# cbm_usb_v1_1a.net
KiCad netlist of a schematic drawn in EAGLE
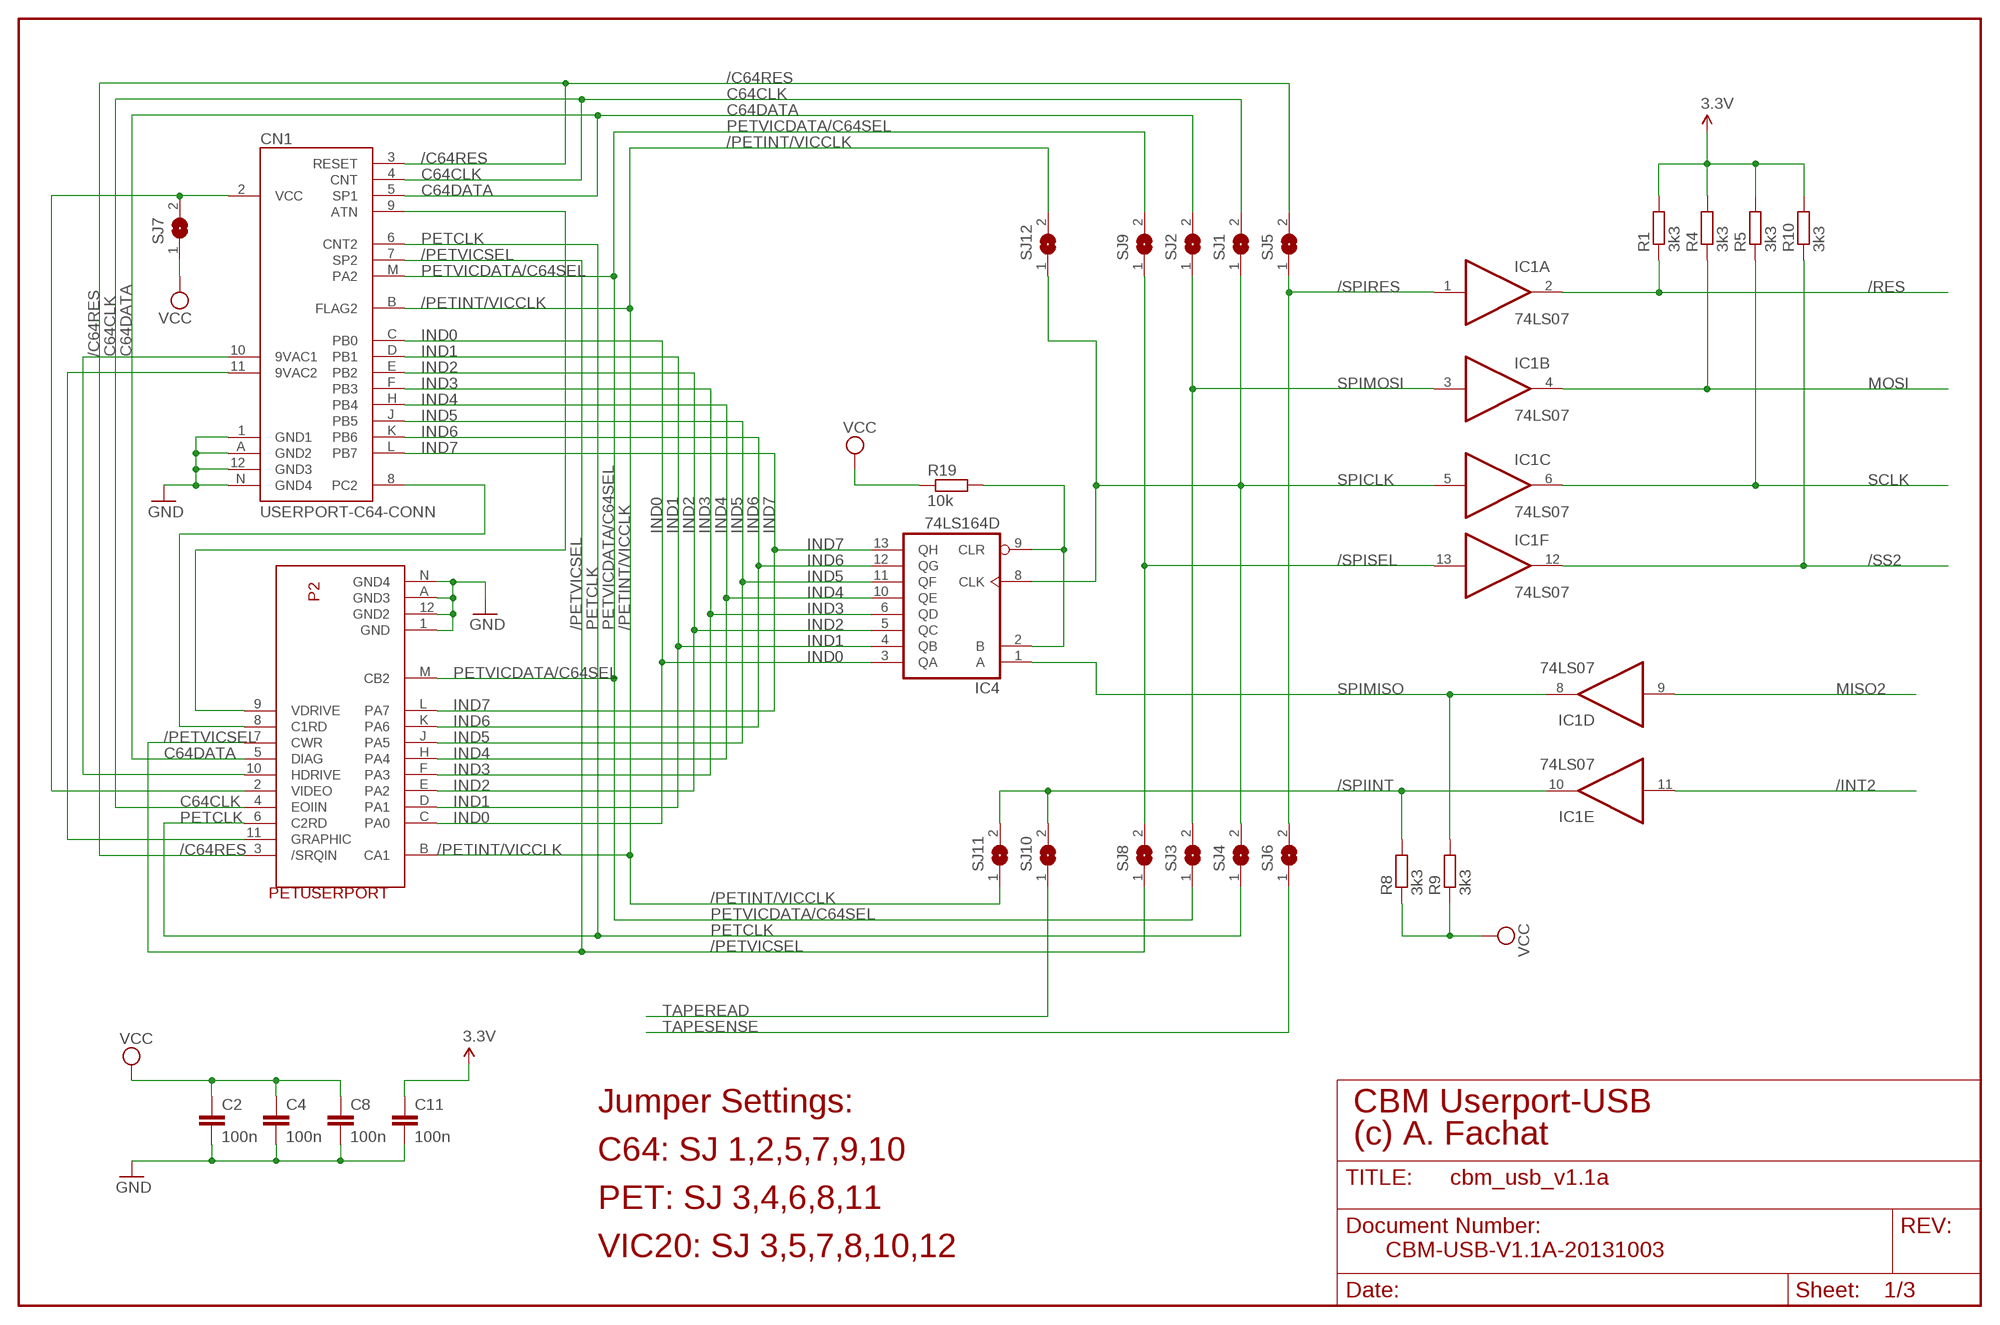
[diagram p0: schematic, sheet 1]
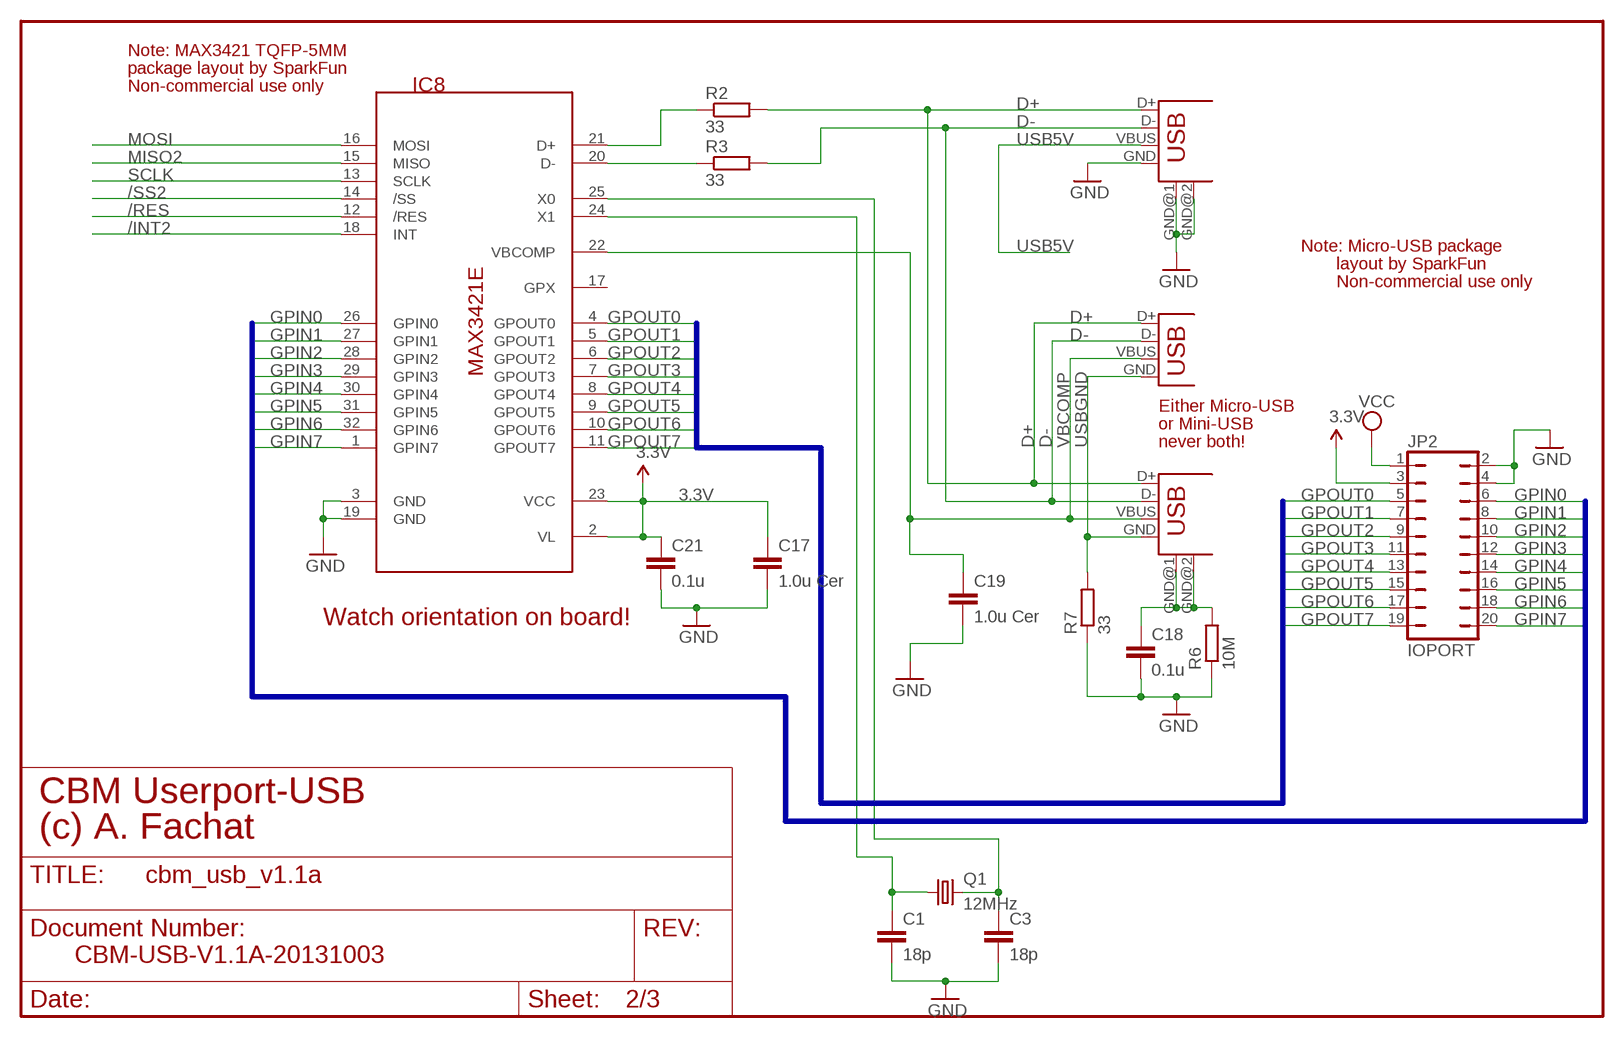
[diagram p1: schematic, sheet 2]
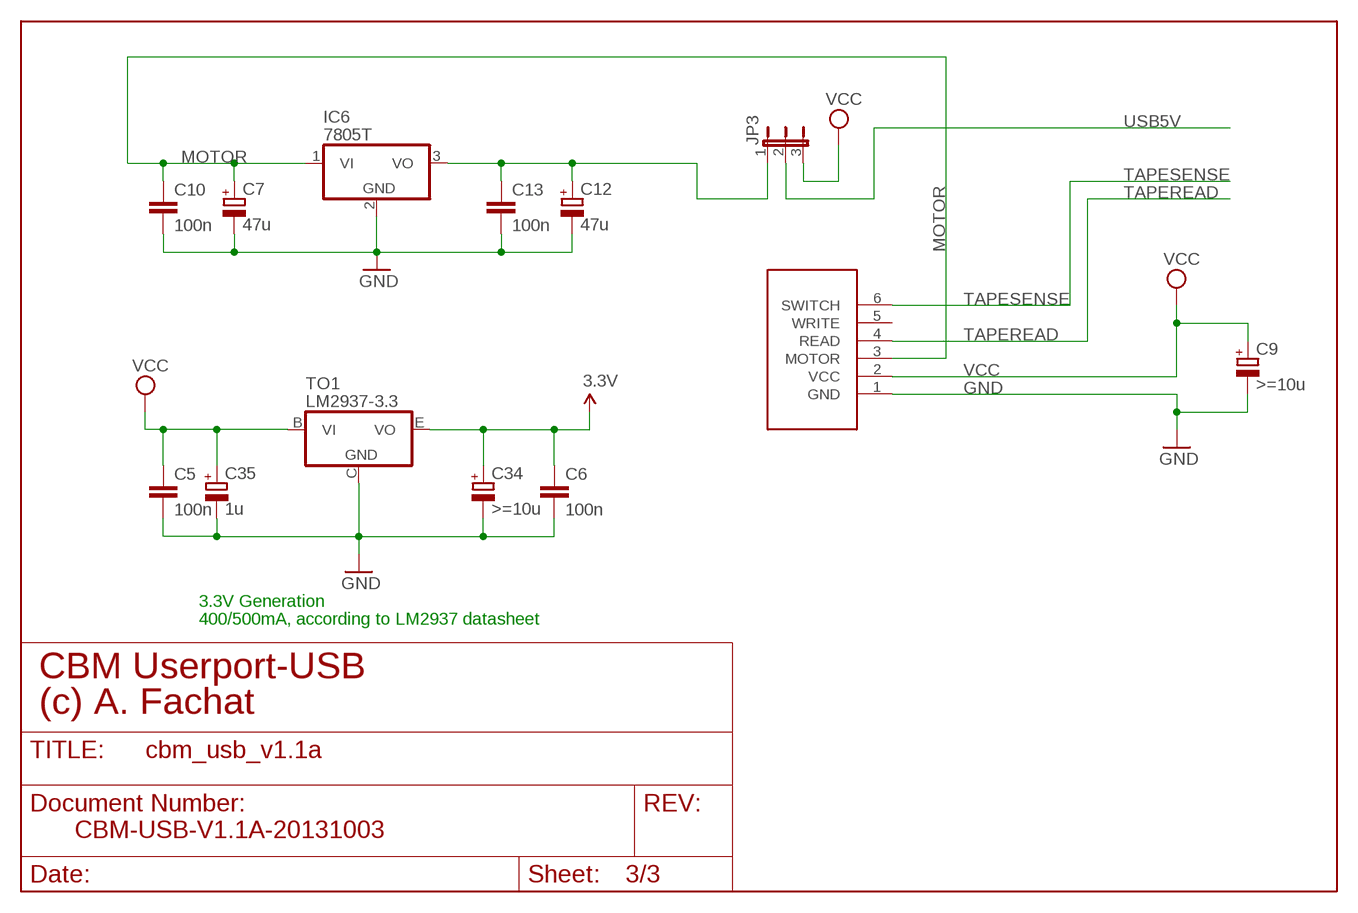
[diagram p2: schematic, sheet 3]

(export (version "E")
  (design (tool "Eeschema 10.0.6"))
  (components
    (comp (ref "C2")
      (value "100n")
      (footprint "eagle-import:C050-025X075")
      (libsource (lib "eagle-import") (part "C-EU050-025X075"))
    )
    (comp (ref "C4")
      (value "100n")
      (footprint "eagle-import:C050-025X075")
      (libsource (lib "eagle-import") (part "C-EU050-025X075"))
    )
    (comp (ref "C8")
      (value "100n")
      (footprint "eagle-import:C050-025X075")
      (libsource (lib "eagle-import") (part "C-EU050-025X075"))
    )
    (comp (ref "C11")
      (value "100n")
      (footprint "eagle-import:C050-025X075")
      (libsource (lib "eagle-import") (part "C-EU050-025X075"))
    )
    (comp (ref "CN1")
      (value "USERPORT-C64-CONN")
      (footprint "eagle-import:UPS24CONN")
      (libsource (lib "eagle-import") (part "USERPORT-C64-CONN"))
    )
    (comp (ref "IC1")
      (value "74LS07")
      (footprint "eagle-import:SO14")
      (libsource (lib "eagle-import") (part "7407DLS"))
    )
    (comp (ref "IC4")
      (value "74LS164D")
      (footprint "eagle-import:SO14")
      (libsource (lib "eagle-import") (part "74164DLS"))
    )
    (comp (ref "P2")
      (value "PETUSERPORT")
      (footprint "eagle-import:FLAT24")
      (libsource (lib "eagle-import") (part "PETUSERPORT"))
    )
    (comp (ref "R1")
      (value "3k3")
      (footprint "eagle-import:0204_7")
      (libsource (lib "eagle-import") (part "R-EU_0204/7"))
    )
    (comp (ref "R4")
      (value "3k3")
      (footprint "eagle-import:0204_7")
      (libsource (lib "eagle-import") (part "R-EU_0204/7"))
    )
    (comp (ref "R5")
      (value "3k3")
      (footprint "eagle-import:0204_7")
      (libsource (lib "eagle-import") (part "R-EU_0204/7"))
    )
    (comp (ref "R8")
      (value "3k3")
      (footprint "eagle-import:0204_7")
      (libsource (lib "eagle-import") (part "R-EU_0204/7"))
    )
    (comp (ref "R9")
      (value "3k3")
      (footprint "eagle-import:0204_7")
      (libsource (lib "eagle-import") (part "R-EU_0204/7"))
    )
    (comp (ref "R10")
      (value "3k3")
      (footprint "eagle-import:0204_7")
      (libsource (lib "eagle-import") (part "R-EU_0204/7"))
    )
    (comp (ref "R19")
      (value "10k")
      (footprint "eagle-import:0204_7")
      (libsource (lib "eagle-import") (part "R-EU_0204/7"))
    )
    (comp (ref "SJ1")
      (value "SJW")
      (footprint "eagle-import:SJW")
      (libsource (lib "eagle-import") (part "SJW"))
    )
    (comp (ref "SJ2")
      (value "SJW")
      (footprint "eagle-import:SJW")
      (libsource (lib "eagle-import") (part "SJW"))
    )
    (comp (ref "SJ3")
      (value "SJW")
      (footprint "eagle-import:SJW")
      (libsource (lib "eagle-import") (part "SJW"))
    )
    (comp (ref "SJ4")
      (value "SJW")
      (footprint "eagle-import:SJW")
      (libsource (lib "eagle-import") (part "SJW"))
    )
    (comp (ref "SJ5")
      (value "SJW")
      (footprint "eagle-import:SJW")
      (libsource (lib "eagle-import") (part "SJW"))
    )
    (comp (ref "SJ6")
      (value "SJW")
      (footprint "eagle-import:SJW")
      (libsource (lib "eagle-import") (part "SJW"))
    )
    (comp (ref "SJ7")
      (value "SJW")
      (footprint "eagle-import:SJW")
      (libsource (lib "eagle-import") (part "SJW"))
    )
    (comp (ref "SJ8")
      (value "SJW")
      (footprint "eagle-import:SJW")
      (libsource (lib "eagle-import") (part "SJW"))
    )
    (comp (ref "SJ9")
      (value "SJW")
      (footprint "eagle-import:SJW")
      (libsource (lib "eagle-import") (part "SJW"))
    )
    (comp (ref "SJ10")
      (value "SJW")
      (footprint "eagle-import:SJW")
      (libsource (lib "eagle-import") (part "SJW"))
    )
    (comp (ref "SJ11")
      (value "SJW")
      (footprint "eagle-import:SJW")
      (libsource (lib "eagle-import") (part "SJW"))
    )
    (comp (ref "SJ12")
      (value "SJW")
      (footprint "eagle-import:SJW")
      (libsource (lib "eagle-import") (part "SJW"))
    )
    (comp (ref "C1")
      (value "18p")
      (footprint "eagle-import:C050-025X075")
      (libsource (lib "eagle-import") (part "C-EU050-025X075"))
    )
    (comp (ref "C3")
      (value "18p")
      (footprint "eagle-import:C050-025X075")
      (libsource (lib "eagle-import") (part "C-EU050-025X075"))
    )
    (comp (ref "C17")
      (value "1.0u Cer")
      (footprint "eagle-import:C050-024X044")
      (libsource (lib "eagle-import") (part "C-EU050-024X044"))
    )
    (comp (ref "C18")
      (value "0.1u")
      (footprint "eagle-import:C050-025X075")
      (libsource (lib "eagle-import") (part "C-EU050-025X075"))
    )
    (comp (ref "C19")
      (value "1.0u Cer")
      (footprint "eagle-import:C050-024X044")
      (libsource (lib "eagle-import") (part "C-EU050-024X044"))
    )
    (comp (ref "C21")
      (value "0.1u")
      (footprint "eagle-import:C050-025X075")
      (libsource (lib "eagle-import") (part "C-EU050-025X075"))
    )
    (comp (ref "IC8")
      (value "MAX3421E")
      (footprint "eagle-import:TQFP32-5MM")
      (libsource (lib "eagle-import") (part "MAX3421E"))
    )
    (comp (ref "JP2")
      (value "IOPORT")
      (footprint "eagle-import:JP10Q")
      (libsource (lib "eagle-import") (part "JP10Q"))
    )
    (comp (ref "Q1")
      (value "12MHz")
      (footprint "eagle-import:HC49U70")
      (libsource (lib "eagle-import") (part "CRYSTALHC49U70"))
    )
    (comp (ref "R2")
      (value "33")
      (footprint "eagle-import:0204_7")
      (libsource (lib "eagle-import") (part "R-EU_0204/7"))
    )
    (comp (ref "R3")
      (value "33")
      (footprint "eagle-import:0204_7")
      (libsource (lib "eagle-import") (part "R-EU_0204/7"))
    )
    (comp (ref "R6")
      (value "10M")
      (footprint "eagle-import:0204_7")
      (libsource (lib "eagle-import") (part "R-EU_0204/7"))
    )
    (comp (ref "R7")
      (value "33")
      (footprint "eagle-import:0204_7")
      (libsource (lib "eagle-import") (part "R-EU_0204/7"))
    )
    (comp (ref "USB1")
      (value "USB-A-H")
      (footprint "eagle-import:USB-A-H")
      (libsource (lib "eagle-import") (part "con-usb-2_USB-A-H"))
    )
    (comp (ref "USB2")
      (value "USB-MB-H")
      (footprint "eagle-import:USB-MB-H")
      (libsource (lib "eagle-import") (part "con-usb-2_USB-MB-H"))
    )
    (comp (ref "X1")
      (value "USB-MICROB")
      (footprint "eagle-import:USB-MICROB")
      (libsource (lib "eagle-import") (part "USB-MICROB"))
    )
    (comp (ref "C5")
      (value "100n")
      (footprint "eagle-import:C050-025X075")
      (libsource (lib "eagle-import") (part "C-EU050-025X075"))
    )
    (comp (ref "C6")
      (value "100n")
      (footprint "eagle-import:C050-025X075")
      (libsource (lib "eagle-import") (part "C-EU050-025X075"))
    )
    (comp (ref "C7")
      (value "47u")
      (footprint "eagle-import:E3,5-8")
      (libsource (lib "eagle-import") (part "CPOL-EUE3.5-8"))
    )
    (comp (ref "C9")
      (value ">=10u")
      (footprint "eagle-import:E5-10,5")
      (libsource (lib "eagle-import") (part "CPOL-EUE5-10.5"))
    )
    (comp (ref "C10")
      (value "100n")
      (footprint "eagle-import:C050-030X075")
      (libsource (lib "eagle-import") (part "C-EU050-030X075"))
    )
    (comp (ref "C12")
      (value "47u")
      (footprint "eagle-import:E3,5-8")
      (libsource (lib "eagle-import") (part "CPOL-EUE3.5-8"))
    )
    (comp (ref "C13")
      (value "100n")
      (footprint "eagle-import:C050-030X075")
      (libsource (lib "eagle-import") (part "C-EU050-030X075"))
    )
    (comp (ref "C34")
      (value ">=10u")
      (footprint "eagle-import:E5-8,5")
      (libsource (lib "eagle-import") (part "CPOL-EUE5-8.5"))
    )
    (comp (ref "C35")
      (value "1u")
      (footprint "eagle-import:E5-8,5")
      (libsource (lib "eagle-import") (part "CPOL-EUE5-8.5"))
    )
    (comp (ref "IC6")
      (value "7805T")
      (footprint "eagle-import:TO220H")
      (libsource (lib "eagle-import") (part "78T05"))
    )
    (comp (ref "JP3")
      (value "JP2E")
      (footprint "eagle-import:JP2")
      (libsource (lib "eagle-import") (part "JP2E"))
    )
    (comp (ref "P3")
      (value "CBMTAPE")
      (footprint "eagle-import:JP6")
      (libsource (lib "eagle-import") (part "CBMTAPE"))
    )
    (comp (ref "TO1")
      (value "LM2937-3.3")
      (footprint "eagle-import:TO220H")
      (libsource (lib "eagle-import") (part "LM2937"))
    )
  )
  (nets
    (net (code "1") (name "3.3V") (class "Default")
      (node (ref "C11") (pin "1") (pinfunction "1_1") (pintype "passive"))
      (node (ref "C17") (pin "1") (pinfunction "1_1") (pintype "passive"))
      (node (ref "C21") (pin "1") (pinfunction "1_1") (pintype "passive"))
      (node (ref "C34") (pin "+") (pinfunction "+_+") (pintype "passive"))
      (node (ref "C6") (pin "1") (pinfunction "1_1") (pintype "passive"))
      (node (ref "IC8") (pin "2") (pinfunction "VL_2") (pintype "power_in"))
      (node (ref "IC8") (pin "23") (pinfunction "VCC_23") (pintype "power_in"))
      (node (ref "JP2") (pin "3") (pinfunction "3_3") (pintype "passive"))
      (node (ref "R1") (pin "2") (pinfunction "2_2") (pintype "passive"))
      (node (ref "R10") (pin "2") (pinfunction "2_2") (pintype "passive"))
      (node (ref "R4") (pin "2") (pinfunction "2_2") (pintype "passive"))
      (node (ref "R5") (pin "2") (pinfunction "2_2") (pintype "passive"))
      (node (ref "TO1") (pin "E") (pinfunction "VO_E") (pintype "passive"))
    )
    (net (code "2") (name "C64CLK") (class "Default")
      (node (ref "CN1") (pin "4") (pinfunction "CNT_4") (pintype "bidirectional"))
      (node (ref "P2") (pin "4") (pinfunction "EOIIN_4") (pintype "bidirectional"))
      (node (ref "SJ1") (pin "2") (pinfunction "2_2") (pintype "passive"))
    )
    (net (code "3") (name "C64DATA") (class "Default")
      (node (ref "CN1") (pin "5") (pinfunction "SP1_5") (pintype "bidirectional"))
      (node (ref "P2") (pin "5") (pinfunction "DIAG_5") (pintype "bidirectional"))
      (node (ref "SJ2") (pin "2") (pinfunction "2_2") (pintype "passive"))
    )
    (net (code "4") (name "D+") (class "Default")
      (node (ref "R2") (pin "2") (pinfunction "2_2") (pintype "passive"))
      (node (ref "USB1") (pin "D+") (pinfunction "D+_D+") (pintype "bidirectional"))
      (node (ref "USB2") (pin "D+") (pinfunction "D+_D+") (pintype "bidirectional"))
      (node (ref "X1") (pin "D+") (pinfunction "D+_D+") (pintype "bidirectional"))
    )
    (net (code "5") (name "D-") (class "Default")
      (node (ref "R3") (pin "2") (pinfunction "2_2") (pintype "passive"))
      (node (ref "USB1") (pin "D-") (pinfunction "D-_D-") (pintype "bidirectional"))
      (node (ref "USB2") (pin "D-") (pinfunction "D-_D-") (pintype "bidirectional"))
      (node (ref "X1") (pin "D-") (pinfunction "D-_D-") (pintype "bidirectional"))
    )
    (net (code "6") (name "GND") (class "Default")
      (node (ref "C1") (pin "2") (pinfunction "2_2") (pintype "passive"))
      (node (ref "C10") (pin "2") (pinfunction "2_2") (pintype "passive"))
      (node (ref "C11") (pin "2") (pinfunction "2_2") (pintype "passive"))
      (node (ref "C12") (pin "-") (pinfunction "-_-") (pintype "passive"))
      (node (ref "C13") (pin "2") (pinfunction "2_2") (pintype "passive"))
      (node (ref "C17") (pin "2") (pinfunction "2_2") (pintype "passive"))
      (node (ref "C18") (pin "2") (pinfunction "2_2") (pintype "passive"))
      (node (ref "C19") (pin "2") (pinfunction "2_2") (pintype "passive"))
      (node (ref "C2") (pin "2") (pinfunction "2_2") (pintype "passive"))
      (node (ref "C21") (pin "2") (pinfunction "2_2") (pintype "passive"))
      (node (ref "C3") (pin "2") (pinfunction "2_2") (pintype "passive"))
      (node (ref "C34") (pin "-") (pinfunction "-_-") (pintype "passive"))
      (node (ref "C35") (pin "-") (pinfunction "-_-") (pintype "passive"))
      (node (ref "C4") (pin "2") (pinfunction "2_2") (pintype "passive"))
      (node (ref "C5") (pin "2") (pinfunction "2_2") (pintype "passive"))
      (node (ref "C6") (pin "2") (pinfunction "2_2") (pintype "passive"))
      (node (ref "C7") (pin "-") (pinfunction "-_-") (pintype "passive"))
      (node (ref "C8") (pin "2") (pinfunction "2_2") (pintype "passive"))
      (node (ref "C9") (pin "-") (pinfunction "-_-") (pintype "passive"))
      (node (ref "CN1") (pin "1") (pinfunction "GND1_1") (pintype "passive"))
      (node (ref "CN1") (pin "12") (pinfunction "GND3_12") (pintype "passive"))
      (node (ref "CN1") (pin "A") (pinfunction "GND2_A") (pintype "passive"))
      (node (ref "CN1") (pin "N") (pinfunction "GND4_N") (pintype "passive"))
      (node (ref "IC6") (pin "2") (pinfunction "GND_2") (pintype "passive"))
      (node (ref "IC8") (pin "19") (pinfunction "GND_19") (pintype "power_in"))
      (node (ref "IC8") (pin "3") (pinfunction "GND_3") (pintype "power_in"))
      (node (ref "JP2") (pin "2") (pinfunction "2_2") (pintype "passive"))
      (node (ref "JP2") (pin "4") (pinfunction "4_4") (pintype "passive"))
      (node (ref "P2") (pin "1") (pinfunction "GND_1") (pintype "bidirectional"))
      (node (ref "P2") (pin "12") (pinfunction "GND2_12") (pintype "bidirectional"))
      (node (ref "P2") (pin "A") (pinfunction "GND3_A") (pintype "bidirectional"))
      (node (ref "P2") (pin "N") (pinfunction "GND4_N") (pintype "bidirectional"))
      (node (ref "P3") (pin "1") (pinfunction "GND_1") (pintype "bidirectional"))
      (node (ref "R6") (pin "1") (pinfunction "1_1") (pintype "passive"))
      (node (ref "R7") (pin "1") (pinfunction "1_1") (pintype "passive"))
      (node (ref "TO1") (pin "C") (pinfunction "GND_C") (pintype "passive"))
      (node (ref "USB1") (pin "GND") (pinfunction "GND_GND") (pintype "bidirectional"))
      (node (ref "USB1") (pin "GND@1") (pinfunction "GND_GND@1") (pintype "bidirectional"))
      (node (ref "USB1") (pin "GND@2") (pinfunction "GND_GND@2") (pintype "bidirectional"))
    )
    (net (code "7") (name "GPIN0") (class "Default")
      (node (ref "IC8") (pin "26") (pinfunction "GPIN0_26") (pintype "input"))
      (node (ref "JP2") (pin "6") (pinfunction "6_6") (pintype "passive"))
    )
    (net (code "8") (name "GPIN1") (class "Default")
      (node (ref "IC8") (pin "27") (pinfunction "GPIN1_27") (pintype "input"))
      (node (ref "JP2") (pin "8") (pinfunction "8_8") (pintype "passive"))
    )
    (net (code "9") (name "GPIN2") (class "Default")
      (node (ref "IC8") (pin "28") (pinfunction "GPIN2_28") (pintype "input"))
      (node (ref "JP2") (pin "10") (pinfunction "10_10") (pintype "passive"))
    )
    (net (code "10") (name "GPIN3") (class "Default")
      (node (ref "IC8") (pin "29") (pinfunction "GPIN3_29") (pintype "input"))
      (node (ref "JP2") (pin "12") (pinfunction "12_12") (pintype "passive"))
    )
    (net (code "11") (name "GPIN4") (class "Default")
      (node (ref "IC8") (pin "30") (pinfunction "GPIN4_30") (pintype "input"))
      (node (ref "JP2") (pin "14") (pinfunction "14_14") (pintype "passive"))
    )
    (net (code "12") (name "GPIN5") (class "Default")
      (node (ref "IC8") (pin "31") (pinfunction "GPIN5_31") (pintype "input"))
      (node (ref "JP2") (pin "16") (pinfunction "16_16") (pintype "passive"))
    )
    (net (code "13") (name "GPIN6") (class "Default")
      (node (ref "IC8") (pin "32") (pinfunction "GPIN6_32") (pintype "input"))
      (node (ref "JP2") (pin "18") (pinfunction "18_18") (pintype "passive"))
    )
    (net (code "14") (name "GPIN7") (class "Default")
      (node (ref "IC8") (pin "1") (pinfunction "GPIN7_1") (pintype "input"))
      (node (ref "JP2") (pin "20") (pinfunction "20_20") (pintype "passive"))
    )
    (net (code "15") (name "GPOUT0") (class "Default")
      (node (ref "IC8") (pin "4") (pinfunction "GPOUT0_4") (pintype "output"))
      (node (ref "JP2") (pin "5") (pinfunction "5_5") (pintype "passive"))
    )
    (net (code "16") (name "GPOUT1") (class "Default")
      (node (ref "IC8") (pin "5") (pinfunction "GPOUT1_5") (pintype "output"))
      (node (ref "JP2") (pin "7") (pinfunction "7_7") (pintype "passive"))
    )
    (net (code "17") (name "GPOUT2") (class "Default")
      (node (ref "IC8") (pin "6") (pinfunction "GPOUT2_6") (pintype "output"))
      (node (ref "JP2") (pin "9") (pinfunction "9_9") (pintype "passive"))
    )
    (net (code "18") (name "GPOUT3") (class "Default")
      (node (ref "IC8") (pin "7") (pinfunction "GPOUT3_7") (pintype "output"))
      (node (ref "JP2") (pin "11") (pinfunction "11_11") (pintype "passive"))
    )
    (net (code "19") (name "GPOUT4") (class "Default")
      (node (ref "IC8") (pin "8") (pinfunction "GPOUT4_8") (pintype "output"))
      (node (ref "JP2") (pin "13") (pinfunction "13_13") (pintype "passive"))
    )
    (net (code "20") (name "GPOUT5") (class "Default")
      (node (ref "IC8") (pin "9") (pinfunction "GPOUT5_9") (pintype "output"))
      (node (ref "JP2") (pin "15") (pinfunction "15_15") (pintype "passive"))
    )
    (net (code "21") (name "GPOUT6") (class "Default")
      (node (ref "IC8") (pin "10") (pinfunction "GPOUT6_10") (pintype "output"))
      (node (ref "JP2") (pin "17") (pinfunction "17_17") (pintype "passive"))
    )
    (net (code "22") (name "GPOUT7") (class "Default")
      (node (ref "IC8") (pin "11") (pinfunction "GPOUT7_11") (pintype "output"))
      (node (ref "JP2") (pin "19") (pinfunction "19_19") (pintype "passive"))
    )
    (net (code "23") (name "IND0") (class "Default")
      (node (ref "CN1") (pin "C") (pinfunction "PB0_C") (pintype "bidirectional"))
      (node (ref "IC4") (pin "3") (pinfunction "QA_3") (pintype "output"))
      (node (ref "P2") (pin "C") (pinfunction "PA0_C") (pintype "bidirectional"))
    )
    (net (code "24") (name "IND1") (class "Default")
      (node (ref "CN1") (pin "D") (pinfunction "PB1_D") (pintype "bidirectional"))
      (node (ref "IC4") (pin "4") (pinfunction "QB_4") (pintype "output"))
      (node (ref "P2") (pin "D") (pinfunction "PA1_D") (pintype "bidirectional"))
    )
    (net (code "25") (name "IND2") (class "Default")
      (node (ref "CN1") (pin "E") (pinfunction "PB2_E") (pintype "bidirectional"))
      (node (ref "IC4") (pin "5") (pinfunction "QC_5") (pintype "output"))
      (node (ref "P2") (pin "E") (pinfunction "PA2_E") (pintype "bidirectional"))
    )
    (net (code "26") (name "IND3") (class "Default")
      (node (ref "CN1") (pin "F") (pinfunction "PB3_F") (pintype "bidirectional"))
      (node (ref "IC4") (pin "6") (pinfunction "QD_6") (pintype "output"))
      (node (ref "P2") (pin "F") (pinfunction "PA3_F") (pintype "bidirectional"))
    )
    (net (code "27") (name "IND4") (class "Default")
      (node (ref "CN1") (pin "H") (pinfunction "PB4_H") (pintype "bidirectional"))
      (node (ref "IC4") (pin "10") (pinfunction "QE_10") (pintype "output"))
      (node (ref "P2") (pin "H") (pinfunction "PA4_H") (pintype "bidirectional"))
    )
    (net (code "28") (name "IND5") (class "Default")
      (node (ref "CN1") (pin "J") (pinfunction "PB5_J") (pintype "bidirectional"))
      (node (ref "IC4") (pin "11") (pinfunction "QF_11") (pintype "output"))
      (node (ref "P2") (pin "J") (pinfunction "PA5_J") (pintype "bidirectional"))
    )
    (net (code "29") (name "IND6") (class "Default")
      (node (ref "CN1") (pin "K") (pinfunction "PB6_K") (pintype "bidirectional"))
      (node (ref "IC4") (pin "12") (pinfunction "QG_12") (pintype "output"))
      (node (ref "P2") (pin "K") (pinfunction "PA6_K") (pintype "bidirectional"))
    )
    (net (code "30") (name "IND7") (class "Default")
      (node (ref "CN1") (pin "L") (pinfunction "PB7_L") (pintype "bidirectional"))
      (node (ref "IC4") (pin "13") (pinfunction "QH_13") (pintype "output"))
      (node (ref "P2") (pin "L") (pinfunction "PA7_L") (pintype "bidirectional"))
    )
    (net (code "31") (name "MISO2") (class "Default")
      (node (ref "IC1") (pin "9") (pinfunction "I_9") (pintype "input"))
      (node (ref "IC8") (pin "15") (pinfunction "MISO_15") (pintype "output"))
    )
    (net (code "32") (name "MOSI") (class "Default")
      (node (ref "IC1") (pin "4") (pinfunction "O_4") (pintype "open_collector"))
      (node (ref "IC8") (pin "16") (pinfunction "MOSI_16") (pintype "input"))
      (node (ref "R4") (pin "1") (pinfunction "1_1") (pintype "passive"))
    )
    (net (code "33") (name "MOTOR") (class "Default")
      (node (ref "C10") (pin "1") (pinfunction "1_1") (pintype "passive"))
      (node (ref "C7") (pin "+") (pinfunction "+_+") (pintype "passive"))
      (node (ref "IC6") (pin "1") (pinfunction "VI_1") (pintype "input"))
      (node (ref "P3") (pin "3") (pinfunction "MOTOR_3") (pintype "bidirectional"))
    )
    (net (code "34") (name "Net-(C18-Pad1)") (class "Default")
      (node (ref "C18") (pin "1") (pinfunction "1_1") (pintype "passive"))
      (node (ref "R6") (pin "2") (pinfunction "2_2") (pintype "passive"))
      (node (ref "USB2") (pin "GND@1") (pinfunction "GND_GND@1") (pintype "bidirectional"))
      (node (ref "USB2") (pin "GND@2") (pinfunction "GND_GND@2") (pintype "bidirectional"))
    )
    (net (code "35") (name "Net-(CN1-9VAC1)") (class "Default")
      (node (ref "CN1") (pin "10") (pinfunction "9VAC1_10") (pintype "output"))
      (node (ref "P2") (pin "10") (pinfunction "HDRIVE_10") (pintype "bidirectional"))
    )
    (net (code "36") (name "Net-(CN1-9VAC2)") (class "Default")
      (node (ref "CN1") (pin "11") (pinfunction "9VAC2_11") (pintype "output"))
      (node (ref "P2") (pin "11") (pinfunction "GRAPHIC_11") (pintype "bidirectional"))
    )
    (net (code "37") (name "Net-(CN1-ATN)") (class "Default")
      (node (ref "CN1") (pin "9") (pinfunction "ATN_9") (pintype "bidirectional"))
      (node (ref "P2") (pin "9") (pinfunction "VDRIVE_9") (pintype "bidirectional"))
    )
    (net (code "38") (name "Net-(CN1-PC2)") (class "Default")
      (node (ref "CN1") (pin "8") (pinfunction "PC2_8") (pintype "bidirectional"))
      (node (ref "P2") (pin "8") (pinfunction "C1RD_8") (pintype "bidirectional"))
    )
    (net (code "39") (name "Net-(CN1-VCC)") (class "Default")
      (node (ref "CN1") (pin "2") (pinfunction "VCC_2") (pintype "passive"))
      (node (ref "P2") (pin "2") (pinfunction "VIDEO_2") (pintype "bidirectional"))
      (node (ref "SJ7") (pin "2") (pinfunction "2_2") (pintype "passive"))
    )
    (net (code "40") (name "Net-(IC4A-B)") (class "Default")
      (node (ref "IC4") (pin "2") (pinfunction "B_2") (pintype "input"))
      (node (ref "IC4") (pin "9") (pinfunction "CLR_9") (pintype "input"))
      (node (ref "R19") (pin "2") (pinfunction "2_2") (pintype "passive"))
    )
    (net (code "41") (name "Net-(IC6-VO)") (class "Default")
      (node (ref "C12") (pin "+") (pinfunction "+_+") (pintype "passive"))
      (node (ref "C13") (pin "1") (pinfunction "1_1") (pintype "passive"))
      (node (ref "IC6") (pin "3") (pinfunction "VO_3") (pintype "passive"))
      (node (ref "JP3") (pin "1") (pinfunction "1_1") (pintype "passive"))
    )
    (net (code "42") (name "Net-(IC8-D+)") (class "Default")
      (node (ref "IC8") (pin "21") (pinfunction "D+_21") (pintype "bidirectional"))
      (node (ref "R2") (pin "1") (pinfunction "1_1") (pintype "passive"))
    )
    (net (code "43") (name "Net-(IC8-D-)") (class "Default")
      (node (ref "IC8") (pin "20") (pinfunction "D-_20") (pintype "bidirectional"))
      (node (ref "R3") (pin "1") (pinfunction "1_1") (pintype "passive"))
    )
    (net (code "44") (name "Net-(IC8-X0)") (class "Default")
      (node (ref "C3") (pin "1") (pinfunction "1_1") (pintype "passive"))
      (node (ref "IC8") (pin "25") (pinfunction "X0_25") (pintype "bidirectional"))
      (node (ref "Q1") (pin "2") (pinfunction "2_2") (pintype "passive"))
    )
    (net (code "45") (name "Net-(IC8-X1)") (class "Default")
      (node (ref "C1") (pin "1") (pinfunction "1_1") (pintype "passive"))
      (node (ref "IC8") (pin "24") (pinfunction "X1_24") (pintype "bidirectional"))
      (node (ref "Q1") (pin "1") (pinfunction "1_1") (pintype "passive"))
    )
    (net (code "46") (name "PETCLK") (class "Default")
      (node (ref "CN1") (pin "6") (pinfunction "CNT2_6") (pintype "bidirectional"))
      (node (ref "P2") (pin "6") (pinfunction "C2RD_6") (pintype "bidirectional"))
      (node (ref "SJ4") (pin "1") (pinfunction "1_1") (pintype "passive"))
    )
    (net (code "47") (name "PETVICDATA{slash}C64SEL") (class "Default")
      (node (ref "CN1") (pin "M") (pinfunction "PA2_M") (pintype "bidirectional"))
      (node (ref "P2") (pin "M") (pinfunction "CB2_M") (pintype "bidirectional"))
      (node (ref "SJ3") (pin "1") (pinfunction "1_1") (pintype "passive"))
      (node (ref "SJ9") (pin "2") (pinfunction "2_2") (pintype "passive"))
    )
    (net (code "48") (name "SCLK") (class "Default")
      (node (ref "IC1") (pin "6") (pinfunction "O_6") (pintype "open_collector"))
      (node (ref "IC8") (pin "13") (pinfunction "SCLK_13") (pintype "input"))
      (node (ref "R5") (pin "1") (pinfunction "1_1") (pintype "passive"))
    )
    (net (code "49") (name "SPICLK") (class "Default")
      (node (ref "IC1") (pin "5") (pinfunction "I_5") (pintype "input"))
      (node (ref "IC4") (pin "8") (pinfunction "CLK_8") (pintype "input"))
      (node (ref "SJ1") (pin "1") (pinfunction "1_1") (pintype "passive"))
      (node (ref "SJ12") (pin "1") (pinfunction "1_1") (pintype "passive"))
      (node (ref "SJ4") (pin "2") (pinfunction "2_2") (pintype "passive"))
    )
    (net (code "50") (name "SPIMISO") (class "Default")
      (node (ref "IC1") (pin "8") (pinfunction "O_8") (pintype "open_collector"))
      (node (ref "IC4") (pin "1") (pinfunction "A_1") (pintype "input"))
      (node (ref "R9") (pin "2") (pinfunction "2_2") (pintype "passive"))
    )
    (net (code "51") (name "SPIMOSI") (class "Default")
      (node (ref "IC1") (pin "3") (pinfunction "I_3") (pintype "input"))
      (node (ref "SJ2") (pin "1") (pinfunction "1_1") (pintype "passive"))
      (node (ref "SJ3") (pin "2") (pinfunction "2_2") (pintype "passive"))
    )
    (net (code "52") (name "TAPEREAD") (class "Default")
      (node (ref "P3") (pin "4") (pinfunction "READ_4") (pintype "bidirectional"))
      (node (ref "SJ10") (pin "1") (pinfunction "1_1") (pintype "passive"))
    )
    (net (code "53") (name "TAPESENSE") (class "Default")
      (node (ref "P3") (pin "6") (pinfunction "SWITCH_6") (pintype "bidirectional"))
      (node (ref "SJ6") (pin "1") (pinfunction "1_1") (pintype "passive"))
    )
    (net (code "54") (name "USB5V") (class "Default")
      (node (ref "JP3") (pin "2") (pinfunction "2_2") (pintype "passive"))
      (node (ref "USB1") (pin "VBUS") (pinfunction "VBUS_VBUS") (pintype "bidirectional"))
    )
    (net (code "55") (name "USBGND") (class "Default")
      (node (ref "R7") (pin "2") (pinfunction "2_2") (pintype "passive"))
      (node (ref "USB2") (pin "GND") (pinfunction "GND_GND") (pintype "bidirectional"))
      (node (ref "X1") (pin "GND") (pinfunction "GND_GND") (pintype "bidirectional"))
    )
    (net (code "56") (name "VBCOMP") (class "Default")
      (node (ref "C19") (pin "1") (pinfunction "1_1") (pintype "passive"))
      (node (ref "IC8") (pin "22") (pinfunction "VBCOMP_22") (pintype "bidirectional"))
      (node (ref "USB2") (pin "VBUS") (pinfunction "VBUS_VBUS") (pintype "bidirectional"))
      (node (ref "X1") (pin "VBUS") (pinfunction "VBUS_VBUS") (pintype "bidirectional"))
    )
    (net (code "57") (name "VCC") (class "Default")
      (node (ref "C2") (pin "1") (pinfunction "1_1") (pintype "passive"))
      (node (ref "C35") (pin "+") (pinfunction "+_+") (pintype "passive"))
      (node (ref "C4") (pin "1") (pinfunction "1_1") (pintype "passive"))
      (node (ref "C5") (pin "1") (pinfunction "1_1") (pintype "passive"))
      (node (ref "C8") (pin "1") (pinfunction "1_1") (pintype "passive"))
      (node (ref "C9") (pin "+") (pinfunction "+_+") (pintype "passive"))
      (node (ref "JP2") (pin "1") (pinfunction "1_1") (pintype "passive"))
      (node (ref "JP3") (pin "3") (pinfunction "3_3") (pintype "passive"))
      (node (ref "P3") (pin "2") (pinfunction "VCC_2") (pintype "bidirectional"))
      (node (ref "R19") (pin "1") (pinfunction "1_1") (pintype "passive"))
      (node (ref "R8") (pin "1") (pinfunction "1_1") (pintype "passive"))
      (node (ref "R9") (pin "1") (pinfunction "1_1") (pintype "passive"))
      (node (ref "SJ7") (pin "1") (pinfunction "1_1") (pintype "passive"))
      (node (ref "TO1") (pin "B") (pinfunction "VI_B") (pintype "input"))
    )
    (net (code "58") (name "unconnected-(IC8-GPX-Pad17)") (class "Default")
      (node (ref "IC8") (pin "17") (pinfunction "GPX_17") (pintype "bidirectional"))
    )
    (net (code "59") (name "unconnected-(P3-WRITE-Pad5)") (class "Default")
      (node (ref "P3") (pin "5") (pinfunction "WRITE_5") (pintype "bidirectional"))
    )
    (net (code "60") (name "{slash}C64RES") (class "Default")
      (node (ref "CN1") (pin "3") (pinfunction "RESET_3") (pintype "bidirectional"))
      (node (ref "P2") (pin "3") (pinfunction "/SRQIN_3") (pintype "bidirectional"))
      (node (ref "SJ5") (pin "2") (pinfunction "2_2") (pintype "passive"))
    )
    (net (code "61") (name "{slash}INT2") (class "Default")
      (node (ref "IC1") (pin "11") (pinfunction "I_11") (pintype "input"))
      (node (ref "IC8") (pin "18") (pinfunction "INT_18") (pintype "output"))
    )
    (net (code "62") (name "{slash}PETINT{slash}VICCLK") (class "Default")
      (node (ref "CN1") (pin "B") (pinfunction "FLAG2_B") (pintype "input"))
      (node (ref "P2") (pin "B") (pinfunction "CA1_B") (pintype "bidirectional"))
      (node (ref "SJ11") (pin "1") (pinfunction "1_1") (pintype "passive"))
      (node (ref "SJ12") (pin "2") (pinfunction "2_2") (pintype "passive"))
    )
    (net (code "63") (name "{slash}PETVICSEL") (class "Default")
      (node (ref "CN1") (pin "7") (pinfunction "SP2_7") (pintype "bidirectional"))
      (node (ref "P2") (pin "7") (pinfunction "CWR_7") (pintype "bidirectional"))
      (node (ref "SJ8") (pin "1") (pinfunction "1_1") (pintype "passive"))
    )
    (net (code "64") (name "{slash}RES") (class "Default")
      (node (ref "IC1") (pin "2") (pinfunction "O_2") (pintype "open_collector"))
      (node (ref "IC8") (pin "12") (pinfunction "/RES_12") (pintype "input"))
      (node (ref "R1") (pin "1") (pinfunction "1_1") (pintype "passive"))
    )
    (net (code "65") (name "{slash}SPIINT") (class "Default")
      (node (ref "IC1") (pin "10") (pinfunction "O_10") (pintype "open_collector"))
      (node (ref "R8") (pin "2") (pinfunction "2_2") (pintype "passive"))
      (node (ref "SJ10") (pin "2") (pinfunction "2_2") (pintype "passive"))
      (node (ref "SJ11") (pin "2") (pinfunction "2_2") (pintype "passive"))
    )
    (net (code "66") (name "{slash}SPIRES") (class "Default")
      (node (ref "IC1") (pin "1") (pinfunction "I_1") (pintype "input"))
      (node (ref "SJ5") (pin "1") (pinfunction "1_1") (pintype "passive"))
      (node (ref "SJ6") (pin "2") (pinfunction "2_2") (pintype "passive"))
    )
    (net (code "67") (name "{slash}SPISEL") (class "Default")
      (node (ref "IC1") (pin "13") (pinfunction "I_13") (pintype "input"))
      (node (ref "SJ8") (pin "2") (pinfunction "2_2") (pintype "passive"))
      (node (ref "SJ9") (pin "1") (pinfunction "1_1") (pintype "passive"))
    )
    (net (code "68") (name "{slash}SS2") (class "Default")
      (node (ref "IC1") (pin "12") (pinfunction "O_12") (pintype "open_collector"))
      (node (ref "IC8") (pin "14") (pinfunction "/SS_14") (pintype "input"))
      (node (ref "R10") (pin "1") (pinfunction "1_1") (pintype "passive"))
    )
  )
)
